# v1_0.net
KiCad netlist of a schematic drawn in Altium Designer
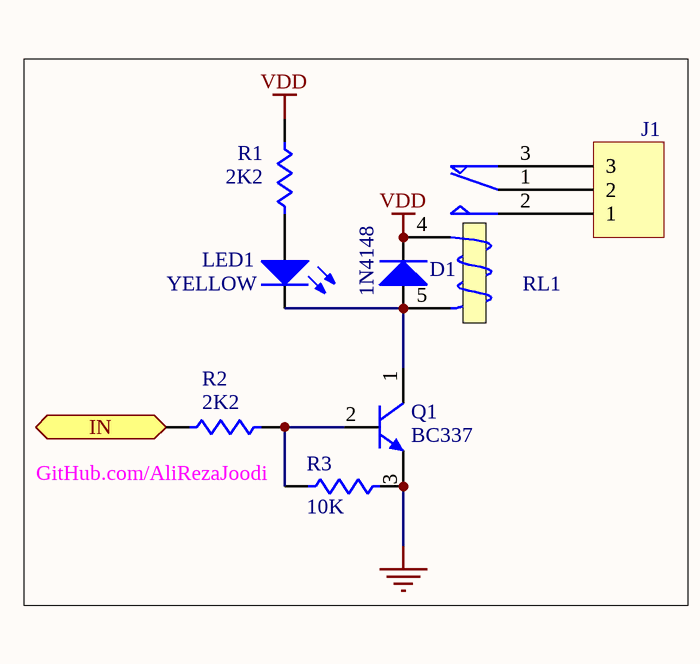
[diagram p0: v1.0.SchDoc]

(export (version "E")
  (design (tool "Eeschema 10.0.6"))
  (components
    (comp (ref "D1")
      (value "1N4148")
      (footprint "DIODE0.4_Glass")
      (description "Default Diode")
      (fields (field (name "MANUFACTURER") "Generic Components") (field (name "PUBLISHER") "Altium Limited"))
      (libsource (lib "Miscellaneous Devices") (part "Diode"))
    )
    (comp (ref "J1")
      (value "3PIN")
      (footprint "Fonics_3PIN_1")
      (description "Header, 3-Pin")
      (fields (field (name "MANUFACTURER") "Generic Components") (field (name "PUBLISHER") "Altium Limited"))
      (libsource (lib "Miscellaneous Connectors") (part "Header 3"))
    )
    (comp (ref "LED1")
      (value "YELLOW")
      (footprint "LED_5mm")
      (description "Typical INFRARED GaAs LED")
      (fields (field (name "MANUFACTURER") "Generic Components") (field (name "PUBLISHER") "Altium Limited"))
      (libsource (lib "my Libraries") (part "Optical Transmitter"))
    )
    (comp (ref "Q1")
      (value "BC337")
      (footprint "TO92C")
      (description "NPN Bipolar Transistor")
      (fields (field (name "MANUFACTURER") "Generic Components") (field (name "PUBLISHER") "Altium Limited"))
      (libsource (lib "Miscellaneous Devices") (part "NPN"))
    )
    (comp (ref "R1")
      (value "2K2")
      (footprint "AXIAL-0.4")
      (description "Resistor")
      (fields (field (name "MANUFACTURER") "Generic Components") (field (name "PUBLISHER") "Altium Limited"))
      (libsource (lib "Miscellaneous Devices") (part "Res1"))
    )
    (comp (ref "R2")
      (value "2K2")
      (footprint "AXIAL-0.4")
      (description "Resistor")
      (fields (field (name "MANUFACTURER") "Generic Components") (field (name "PUBLISHER") "Altium Limited"))
      (libsource (lib "Miscellaneous Devices") (part "Res1"))
    )
    (comp (ref "R3")
      (value "10K")
      (footprint "AXIAL-0.4")
      (description "Resistor")
      (fields (field (name "MANUFACTURER") "Generic Components") (field (name "PUBLISHER") "Altium Limited"))
      (libsource (lib "Miscellaneous Devices") (part "Res1"))
    )
    (comp (ref "RL1")
      (value "12V")
      (footprint "RELAY-SPDT-1")
      (description "SPDT Relay")
      (fields (field (name "MANUFACTURER") "Generic Components") (field (name "PUBLISHER") "Altium Limited"))
      (libsource (lib "Miscellaneous Devices") (part "Relay-SPDT_2"))
    )
  )
  (nets
    (net (code "1") (name "/IN") (class "Default")
      (node (ref "R2") (pin "2") (pinfunction "2_2") (pintype "passive"))
    )
    (net (code "2") (name "GND") (class "Default")
      (node (ref "Q1") (pin "3") (pinfunction "E_3") (pintype "passive"))
      (node (ref "R3") (pin "1") (pinfunction "1_1") (pintype "passive"))
    )
    (net (code "3") (name "Net-(D1-A)") (class "Default")
      (node (ref "D1") (pin "1") (pinfunction "A_1") (pintype "passive"))
      (node (ref "LED1") (pin "2") (pinfunction "K_2") (pintype "passive"))
      (node (ref "Q1") (pin "1") (pinfunction "C_1") (pintype "passive"))
      (node (ref "RL1") (pin "5") (pinfunction "T2_5") (pintype "passive"))
    )
    (net (code "4") (name "Net-(LED1-A)") (class "Default")
      (node (ref "LED1") (pin "1") (pinfunction "A_1") (pintype "passive"))
      (node (ref "R1") (pin "2") (pinfunction "2_2") (pintype "passive"))
    )
    (net (code "5") (name "Net-(Q1-B)") (class "Default")
      (node (ref "Q1") (pin "2") (pinfunction "B_2") (pintype "passive"))
      (node (ref "R2") (pin "1") (pinfunction "1_1") (pintype "passive"))
      (node (ref "R3") (pin "2") (pinfunction "2_2") (pintype "passive"))
    )
    (net (code "6") (name "Net-(RL1-COM)") (class "Default")
      (node (ref "J1") (pin "2") (pinfunction "2_2") (pintype "passive"))
      (node (ref "RL1") (pin "1") (pinfunction "COM_1") (pintype "passive"))
    )
    (net (code "7") (name "Net-(RL1-NC)") (class "Default")
      (node (ref "J1") (pin "3") (pinfunction "3_3") (pintype "passive"))
      (node (ref "RL1") (pin "3") (pinfunction "NC_3") (pintype "passive"))
    )
    (net (code "8") (name "Net-(RL1-NO)") (class "Default")
      (node (ref "J1") (pin "1") (pinfunction "1_1") (pintype "passive"))
      (node (ref "RL1") (pin "2") (pinfunction "NO_2") (pintype "passive"))
    )
    (net (code "9") (name "VDD") (class "Default")
      (node (ref "D1") (pin "2") (pinfunction "K_2") (pintype "passive"))
      (node (ref "R1") (pin "1") (pinfunction "1_1") (pintype "passive"))
      (node (ref "RL1") (pin "4") (pinfunction "T1_4") (pintype "passive"))
    )
  )
)
